# crazypi.net
KiCad netlist of a schematic drawn in EAGLE
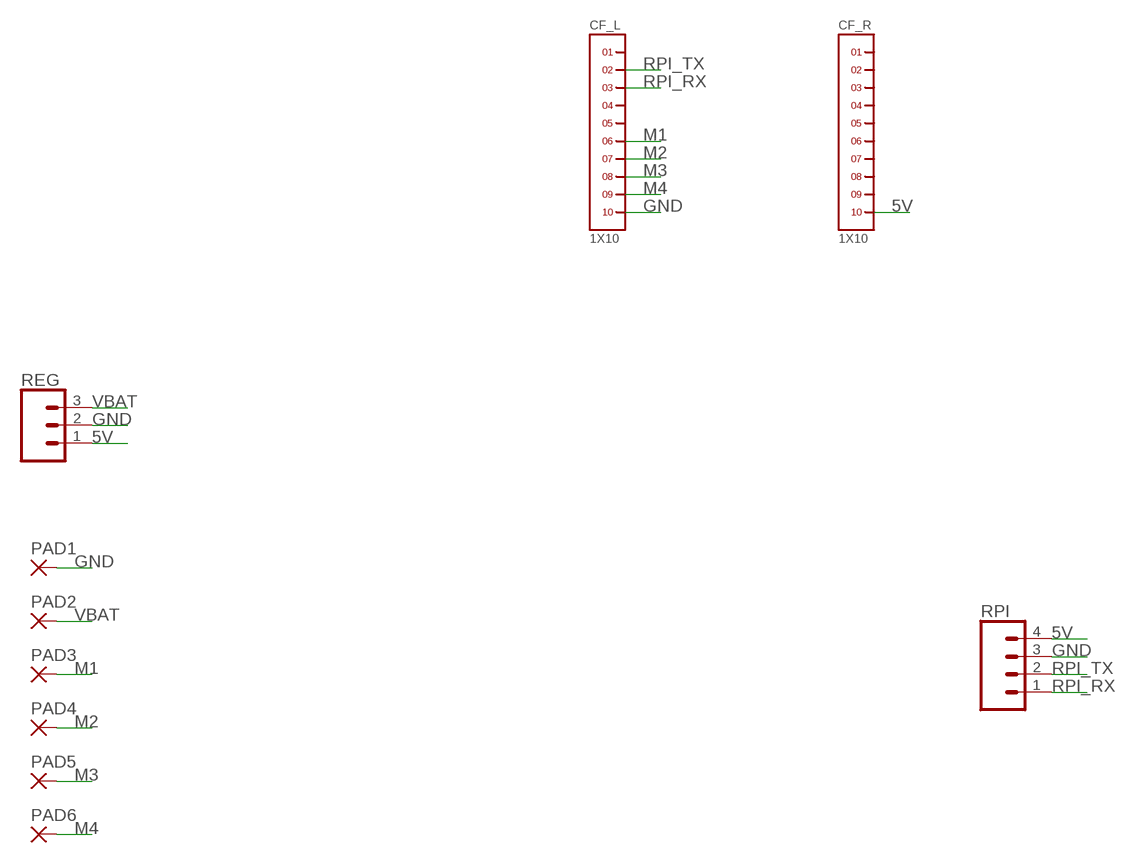
[diagram p0: schematic, sheet 1]

(export (version "E")
  (design (tool "Eeschema 10.0.6"))
  (components
    (comp (ref "CF_L")
      (value "1X10")
      (footprint "eagle-import:1X10")
      (libsource (lib "eagle-import") (part "1X10"))
    )
    (comp (ref "CF_R")
      (value "1X10")
      (footprint "eagle-import:1X10")
      (libsource (lib "eagle-import") (part "1X10"))
    )
    (comp (ref "PAD1")
      (value "SMD2")
      (footprint "eagle-import:SMD1,27-2,54")
      (libsource (lib "eagle-import") (part "SMD2"))
    )
    (comp (ref "PAD2")
      (value "SMD2")
      (footprint "eagle-import:SMD1,27-2,54")
      (libsource (lib "eagle-import") (part "SMD2"))
    )
    (comp (ref "PAD3")
      (value "SMD2")
      (footprint "eagle-import:SMD1,27-2,54")
      (libsource (lib "eagle-import") (part "SMD2"))
    )
    (comp (ref "PAD4")
      (value "SMD2")
      (footprint "eagle-import:SMD1,27-2,54")
      (libsource (lib "eagle-import") (part "SMD2"))
    )
    (comp (ref "PAD5")
      (value "SMD2")
      (footprint "eagle-import:SMD1,27-2,54")
      (libsource (lib "eagle-import") (part "SMD2"))
    )
    (comp (ref "PAD6")
      (value "SMD2")
      (footprint "eagle-import:SMD1,27-2,54")
      (libsource (lib "eagle-import") (part "SMD2"))
    )
    (comp (ref "REG")
      (value "CONN_031X03_NO_SILK")
      (footprint "eagle-import:1X03_NO_SILK")
      (libsource (lib "eagle-import") (part "CONN_031X03_NO_SILK"))
    )
    (comp (ref "RPI")
      (value "CONN_041X04_NO_SILK")
      (footprint "eagle-import:1X04_NO_SILK")
      (libsource (lib "eagle-import") (part "CONN_041X04_NO_SILK"))
    )
  )
  (nets
    (net (code "1") (name "/5V") (class "Default")
      (node (ref "CF_R") (pin "10") (pinfunction "10_10") (pintype "bidirectional"))
      (node (ref "REG") (pin "1") (pinfunction "1_1") (pintype "passive"))
      (node (ref "RPI") (pin "4") (pinfunction "4_4") (pintype "passive"))
    )
    (net (code "2") (name "/GND") (class "Default")
      (node (ref "CF_L") (pin "10") (pinfunction "10_10") (pintype "bidirectional"))
      (node (ref "PAD1") (pin "1") (pinfunction "P_1") (pintype "passive"))
      (node (ref "REG") (pin "2") (pinfunction "2_2") (pintype "passive"))
      (node (ref "RPI") (pin "3") (pinfunction "3_3") (pintype "passive"))
    )
    (net (code "3") (name "/M1") (class "Default")
      (node (ref "CF_L") (pin "6") (pinfunction "6_6") (pintype "bidirectional"))
      (node (ref "PAD3") (pin "1") (pinfunction "P_1") (pintype "passive"))
    )
    (net (code "4") (name "/M2") (class "Default")
      (node (ref "CF_L") (pin "7") (pinfunction "7_7") (pintype "bidirectional"))
      (node (ref "PAD4") (pin "1") (pinfunction "P_1") (pintype "passive"))
    )
    (net (code "5") (name "/M3") (class "Default")
      (node (ref "CF_L") (pin "8") (pinfunction "8_8") (pintype "bidirectional"))
      (node (ref "PAD5") (pin "1") (pinfunction "P_1") (pintype "passive"))
    )
    (net (code "6") (name "/M4") (class "Default")
      (node (ref "CF_L") (pin "9") (pinfunction "9_9") (pintype "bidirectional"))
      (node (ref "PAD6") (pin "1") (pinfunction "P_1") (pintype "passive"))
    )
    (net (code "7") (name "/RPI_RX") (class "Default")
      (node (ref "CF_L") (pin "3") (pinfunction "3_3") (pintype "bidirectional"))
      (node (ref "RPI") (pin "1") (pinfunction "1_1") (pintype "passive"))
    )
    (net (code "8") (name "/RPI_TX") (class "Default")
      (node (ref "CF_L") (pin "2") (pinfunction "2_2") (pintype "bidirectional"))
      (node (ref "RPI") (pin "2") (pinfunction "2_2") (pintype "passive"))
    )
    (net (code "9") (name "/VBAT") (class "Default")
      (node (ref "PAD2") (pin "1") (pinfunction "P_1") (pintype "passive"))
      (node (ref "REG") (pin "3") (pinfunction "3_3") (pintype "passive"))
    )
    (net (code "10") (name "unconnected-(CF_L-Pad1)") (class "Default")
      (node (ref "CF_L") (pin "1") (pinfunction "1_1") (pintype "bidirectional"))
    )
    (net (code "11") (name "unconnected-(CF_L-Pad4)") (class "Default")
      (node (ref "CF_L") (pin "4") (pinfunction "4_4") (pintype "bidirectional"))
    )
    (net (code "12") (name "unconnected-(CF_L-Pad5)") (class "Default")
      (node (ref "CF_L") (pin "5") (pinfunction "5_5") (pintype "bidirectional"))
    )
    (net (code "13") (name "unconnected-(CF_R-Pad1)") (class "Default")
      (node (ref "CF_R") (pin "1") (pinfunction "1_1") (pintype "bidirectional"))
    )
    (net (code "14") (name "unconnected-(CF_R-Pad2)") (class "Default")
      (node (ref "CF_R") (pin "2") (pinfunction "2_2") (pintype "bidirectional"))
    )
    (net (code "15") (name "unconnected-(CF_R-Pad3)") (class "Default")
      (node (ref "CF_R") (pin "3") (pinfunction "3_3") (pintype "bidirectional"))
    )
    (net (code "16") (name "unconnected-(CF_R-Pad4)") (class "Default")
      (node (ref "CF_R") (pin "4") (pinfunction "4_4") (pintype "bidirectional"))
    )
    (net (code "17") (name "unconnected-(CF_R-Pad5)") (class "Default")
      (node (ref "CF_R") (pin "5") (pinfunction "5_5") (pintype "bidirectional"))
    )
    (net (code "18") (name "unconnected-(CF_R-Pad6)") (class "Default")
      (node (ref "CF_R") (pin "6") (pinfunction "6_6") (pintype "bidirectional"))
    )
    (net (code "19") (name "unconnected-(CF_R-Pad7)") (class "Default")
      (node (ref "CF_R") (pin "7") (pinfunction "7_7") (pintype "bidirectional"))
    )
    (net (code "20") (name "unconnected-(CF_R-Pad8)") (class "Default")
      (node (ref "CF_R") (pin "8") (pinfunction "8_8") (pintype "bidirectional"))
    )
    (net (code "21") (name "unconnected-(CF_R-Pad9)") (class "Default")
      (node (ref "CF_R") (pin "9") (pinfunction "9_9") (pintype "bidirectional"))
    )
  )
)
